# top.net
KiCad netlist of a schematic drawn in Altium Designer
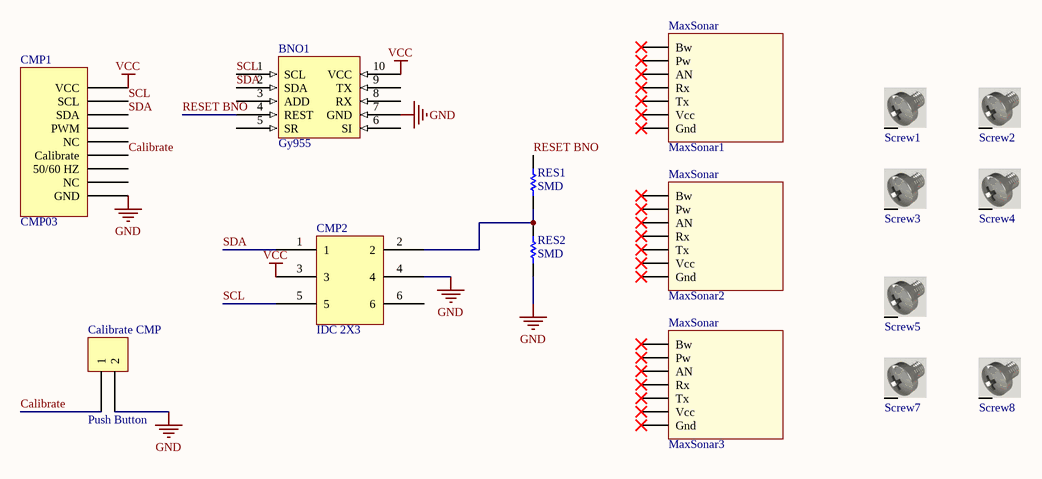
[diagram p0: top.SchDoc]

(export (version "E")
  (design (tool "Eeschema 10.0.6"))
  (components
    (comp (ref "BNO1") (value "Gy955") (footprint "DIP10") (libsource (lib "Farz1") (part "Gy955")))
    (comp (ref "Calibrate CMP")
      (value "Push Button")
      (footprint "Push Button")
      (libsource (lib "Farz1") (part "Push Button"))
    )
    (comp (ref "CMP1") (value "CMP03") (footprint "CMP03") (libsource (lib "Farz1") (part "CMP03")))
    (comp (ref "CMP2") (value "IDC 2X3") (footprint "IDC 2X3") (libsource (lib "Farz1") (part "IDC 2X3")))
    (comp (ref "MaxSonar1")
      (value "Ultrasonic")
      (footprint "MaxSonar")
      (libsource (lib "Farz1") (part "MaxSonar"))
    )
    (comp (ref "MaxSonar2")
      (value "Ultrasonic")
      (footprint "MaxSonar")
      (libsource (lib "Farz1") (part "MaxSonar"))
    )
    (comp (ref "MaxSonar3")
      (value "Ultrasonic")
      (footprint "MaxSonar")
      (libsource (lib "Farz1") (part "MaxSonar"))
    )
    (comp (ref "RES1")
      (value "SMD")
      (footprint "Resistor SMD 1206")
      (libsource (lib "Farz1") (part "Res SMD"))
    )
    (comp (ref "RES2")
      (value "SMD")
      (footprint "Resistor SMD 1206")
      (libsource (lib "Farz1") (part "Res SMD"))
    )
    (comp (ref "Screw1")
      (value "Screw")
      (footprint "Screw")
      (fields (field (name "PUBLISHER") "Altium Limited"))
      (libsource (lib "Farzanegan") (part "Screw"))
    )
    (comp (ref "Screw2")
      (value "Screw")
      (footprint "Screw")
      (fields (field (name "PUBLISHER") "Altium Limited"))
      (libsource (lib "Farzanegan") (part "Screw"))
    )
    (comp (ref "Screw3")
      (value "Screw")
      (footprint "Screw")
      (fields (field (name "PUBLISHER") "Altium Limited"))
      (libsource (lib "Farzanegan") (part "Screw"))
    )
    (comp (ref "Screw4")
      (value "Screw")
      (footprint "Screw")
      (fields (field (name "PUBLISHER") "Altium Limited"))
      (libsource (lib "Farzanegan") (part "Screw"))
    )
    (comp (ref "Screw5")
      (value "Screw")
      (footprint "Screw")
      (fields (field (name "PUBLISHER") "Altium Limited"))
      (libsource (lib "Farzanegan") (part "Screw"))
    )
    (comp (ref "Screw7")
      (value "Screw")
      (footprint "Screw")
      (fields (field (name "PUBLISHER") "Altium Limited"))
      (libsource (lib "Farzanegan") (part "Screw"))
    )
    (comp (ref "Screw8")
      (value "Screw")
      (footprint "Screw")
      (fields (field (name "PUBLISHER") "Altium Limited"))
      (libsource (lib "Farzanegan") (part "Screw"))
    )
  )
  (nets
    (net (code "1") (name "/Calibrate") (class "Default")
      (node (ref "CMP1") (pin "6") (pinfunction "Calibrate_6") (pintype "passive"))
      (node (ref "Calibrate CMP") (pin "1") (pinfunction "1_1") (pintype "passive"))
    )
    (net (code "2") (name "/RESET BNO") (class "Default")
      (node (ref "BNO1") (pin "4") (pinfunction "REST_4") (pintype "input"))
      (node (ref "RES1") (pin "2") (pinfunction "2_2") (pintype "passive"))
    )
    (net (code "3") (name "/SCL") (class "Default")
      (node (ref "BNO1") (pin "1") (pinfunction "SCL_1") (pintype "input"))
      (node (ref "CMP1") (pin "2") (pinfunction "SCL_2") (pintype "passive"))
      (node (ref "CMP2") (pin "5") (pinfunction "5_5") (pintype "passive"))
    )
    (net (code "4") (name "/SDA") (class "Default")
      (node (ref "BNO1") (pin "2") (pinfunction "SDA_2") (pintype "input"))
      (node (ref "CMP1") (pin "3") (pinfunction "SDA_3") (pintype "passive"))
      (node (ref "CMP2") (pin "1") (pinfunction "1_1") (pintype "passive"))
    )
    (net (code "5") (name "GND") (class "Default")
      (node (ref "BNO1") (pin "7") (pinfunction "GND_7") (pintype "input"))
      (node (ref "CMP1") (pin "9") (pinfunction "GND_9") (pintype "passive"))
      (node (ref "CMP2") (pin "4") (pinfunction "4_4") (pintype "passive"))
      (node (ref "Calibrate CMP") (pin "2") (pinfunction "2_2") (pintype "passive"))
      (node (ref "RES2") (pin "1") (pinfunction "1_1") (pintype "passive"))
    )
    (net (code "6") (name "Net-(CMP2-Pad2)") (class "Default")
      (node (ref "CMP2") (pin "2") (pinfunction "2_2") (pintype "passive"))
      (node (ref "RES1") (pin "1") (pinfunction "1_1") (pintype "passive"))
      (node (ref "RES2") (pin "2") (pinfunction "2_2") (pintype "passive"))
    )
    (net (code "7") (name "VCC") (class "Default")
      (node (ref "BNO1") (pin "10") (pinfunction "VCC_10") (pintype "input"))
      (node (ref "CMP1") (pin "1") (pinfunction "VCC_1") (pintype "passive"))
      (node (ref "CMP2") (pin "3") (pinfunction "3_3") (pintype "passive"))
    )
    (net (code "8") (name "unconnected-(BNO1-ADD-Pad3)") (class "Default")
      (node (ref "BNO1") (pin "3") (pinfunction "ADD_3") (pintype "input"))
    )
    (net (code "9") (name "unconnected-(BNO1-RX-Pad8)") (class "Default")
      (node (ref "BNO1") (pin "8") (pinfunction "RX_8") (pintype "input"))
    )
    (net (code "10") (name "unconnected-(BNO1-SI-Pad6)") (class "Default")
      (node (ref "BNO1") (pin "6") (pinfunction "SI_6") (pintype "input"))
    )
    (net (code "11") (name "unconnected-(BNO1-SR-Pad5)") (class "Default")
      (node (ref "BNO1") (pin "5") (pinfunction "SR_5") (pintype "input"))
    )
    (net (code "12") (name "unconnected-(BNO1-TX-Pad9)") (class "Default")
      (node (ref "BNO1") (pin "9") (pinfunction "TX_9") (pintype "input"))
    )
    (net (code "13") (name "unconnected-(CMP1-50{slash}60_HZ-Pad7)") (class "Default")
      (node (ref "CMP1") (pin "7") (pinfunction "50/60_HZ_7") (pintype "passive"))
    )
    (net (code "14") (name "unconnected-(CMP1-NC-Pad5)") (class "Default")
      (node (ref "CMP1") (pin "5") (pinfunction "NC_5") (pintype "passive"))
    )
    (net (code "15") (name "unconnected-(CMP1-NC-Pad8)") (class "Default")
      (node (ref "CMP1") (pin "8") (pinfunction "NC_8") (pintype "passive"))
    )
    (net (code "16") (name "unconnected-(CMP1-PWM-Pad4)") (class "Default")
      (node (ref "CMP1") (pin "4") (pinfunction "PWM_4") (pintype "passive"))
    )
    (net (code "17") (name "unconnected-(CMP2-Pad6)") (class "Default")
      (node (ref "CMP2") (pin "6") (pinfunction "6_6") (pintype "passive"))
    )
    (net (code "18") (name "unconnected-(MaxSonar1-AN-Pad3)") (class "Default")
      (node (ref "MaxSonar1") (pin "3") (pinfunction "AN_3") (pintype "passive+no_connect"))
    )
    (net (code "19") (name "unconnected-(MaxSonar1-Bw-Pad1)") (class "Default")
      (node (ref "MaxSonar1") (pin "1") (pinfunction "Bw_1") (pintype "passive+no_connect"))
    )
    (net (code "20") (name "unconnected-(MaxSonar1-Gnd-Pad7)") (class "Default")
      (node (ref "MaxSonar1") (pin "7") (pinfunction "Gnd_7") (pintype "passive+no_connect"))
    )
    (net (code "21") (name "unconnected-(MaxSonar1-Pw-Pad2)") (class "Default")
      (node (ref "MaxSonar1") (pin "2") (pinfunction "Pw_2") (pintype "passive+no_connect"))
    )
    (net (code "22") (name "unconnected-(MaxSonar1-Rx-Pad4)") (class "Default")
      (node (ref "MaxSonar1") (pin "4") (pinfunction "Rx_4") (pintype "passive+no_connect"))
    )
    (net (code "23") (name "unconnected-(MaxSonar1-Tx-Pad5)") (class "Default")
      (node (ref "MaxSonar1") (pin "5") (pinfunction "Tx_5") (pintype "passive+no_connect"))
    )
    (net (code "24") (name "unconnected-(MaxSonar1-Vcc-Pad6)") (class "Default")
      (node (ref "MaxSonar1") (pin "6") (pinfunction "Vcc_6") (pintype "passive+no_connect"))
    )
    (net (code "25") (name "unconnected-(MaxSonar2-AN-Pad3)") (class "Default")
      (node (ref "MaxSonar2") (pin "3") (pinfunction "AN_3") (pintype "passive+no_connect"))
    )
    (net (code "26") (name "unconnected-(MaxSonar2-Bw-Pad1)") (class "Default")
      (node (ref "MaxSonar2") (pin "1") (pinfunction "Bw_1") (pintype "passive+no_connect"))
    )
    (net (code "27") (name "unconnected-(MaxSonar2-Gnd-Pad7)") (class "Default")
      (node (ref "MaxSonar2") (pin "7") (pinfunction "Gnd_7") (pintype "passive+no_connect"))
    )
    (net (code "28") (name "unconnected-(MaxSonar2-Pw-Pad2)") (class "Default")
      (node (ref "MaxSonar2") (pin "2") (pinfunction "Pw_2") (pintype "passive+no_connect"))
    )
    (net (code "29") (name "unconnected-(MaxSonar2-Rx-Pad4)") (class "Default")
      (node (ref "MaxSonar2") (pin "4") (pinfunction "Rx_4") (pintype "passive+no_connect"))
    )
    (net (code "30") (name "unconnected-(MaxSonar2-Tx-Pad5)") (class "Default")
      (node (ref "MaxSonar2") (pin "5") (pinfunction "Tx_5") (pintype "passive+no_connect"))
    )
    (net (code "31") (name "unconnected-(MaxSonar2-Vcc-Pad6)") (class "Default")
      (node (ref "MaxSonar2") (pin "6") (pinfunction "Vcc_6") (pintype "passive+no_connect"))
    )
    (net (code "32") (name "unconnected-(MaxSonar3-AN-Pad3)") (class "Default")
      (node (ref "MaxSonar3") (pin "3") (pinfunction "AN_3") (pintype "passive+no_connect"))
    )
    (net (code "33") (name "unconnected-(MaxSonar3-Bw-Pad1)") (class "Default")
      (node (ref "MaxSonar3") (pin "1") (pinfunction "Bw_1") (pintype "passive+no_connect"))
    )
    (net (code "34") (name "unconnected-(MaxSonar3-Gnd-Pad7)") (class "Default")
      (node (ref "MaxSonar3") (pin "7") (pinfunction "Gnd_7") (pintype "passive+no_connect"))
    )
    (net (code "35") (name "unconnected-(MaxSonar3-Pw-Pad2)") (class "Default")
      (node (ref "MaxSonar3") (pin "2") (pinfunction "Pw_2") (pintype "passive+no_connect"))
    )
    (net (code "36") (name "unconnected-(MaxSonar3-Rx-Pad4)") (class "Default")
      (node (ref "MaxSonar3") (pin "4") (pinfunction "Rx_4") (pintype "passive+no_connect"))
    )
    (net (code "37") (name "unconnected-(MaxSonar3-Tx-Pad5)") (class "Default")
      (node (ref "MaxSonar3") (pin "5") (pinfunction "Tx_5") (pintype "passive+no_connect"))
    )
    (net (code "38") (name "unconnected-(MaxSonar3-Vcc-Pad6)") (class "Default")
      (node (ref "MaxSonar3") (pin "6") (pinfunction "Vcc_6") (pintype "passive+no_connect"))
    )
    (net (code "39") (name "unconnected-(Screw1-PadS)") (class "Default")
      (node (ref "Screw1") (pin "S") (pinfunction "S_S") (pintype "passive"))
    )
    (net (code "40") (name "unconnected-(Screw2-PadS)") (class "Default")
      (node (ref "Screw2") (pin "S") (pinfunction "S_S") (pintype "passive"))
    )
    (net (code "41") (name "unconnected-(Screw3-PadS)") (class "Default")
      (node (ref "Screw3") (pin "S") (pinfunction "S_S") (pintype "passive"))
    )
    (net (code "42") (name "unconnected-(Screw4-PadS)") (class "Default")
      (node (ref "Screw4") (pin "S") (pinfunction "S_S") (pintype "passive"))
    )
    (net (code "43") (name "unconnected-(Screw5-PadS)") (class "Default")
      (node (ref "Screw5") (pin "S") (pinfunction "S_S") (pintype "passive"))
    )
    (net (code "44") (name "unconnected-(Screw7-PadS)") (class "Default")
      (node (ref "Screw7") (pin "S") (pinfunction "S_S") (pintype "passive"))
    )
    (net (code "45") (name "unconnected-(Screw8-PadS)") (class "Default")
      (node (ref "Screw8") (pin "S") (pinfunction "S_S") (pintype "passive"))
    )
  )
)
